# sanguino.net
KiCad netlist of a schematic drawn in EAGLE
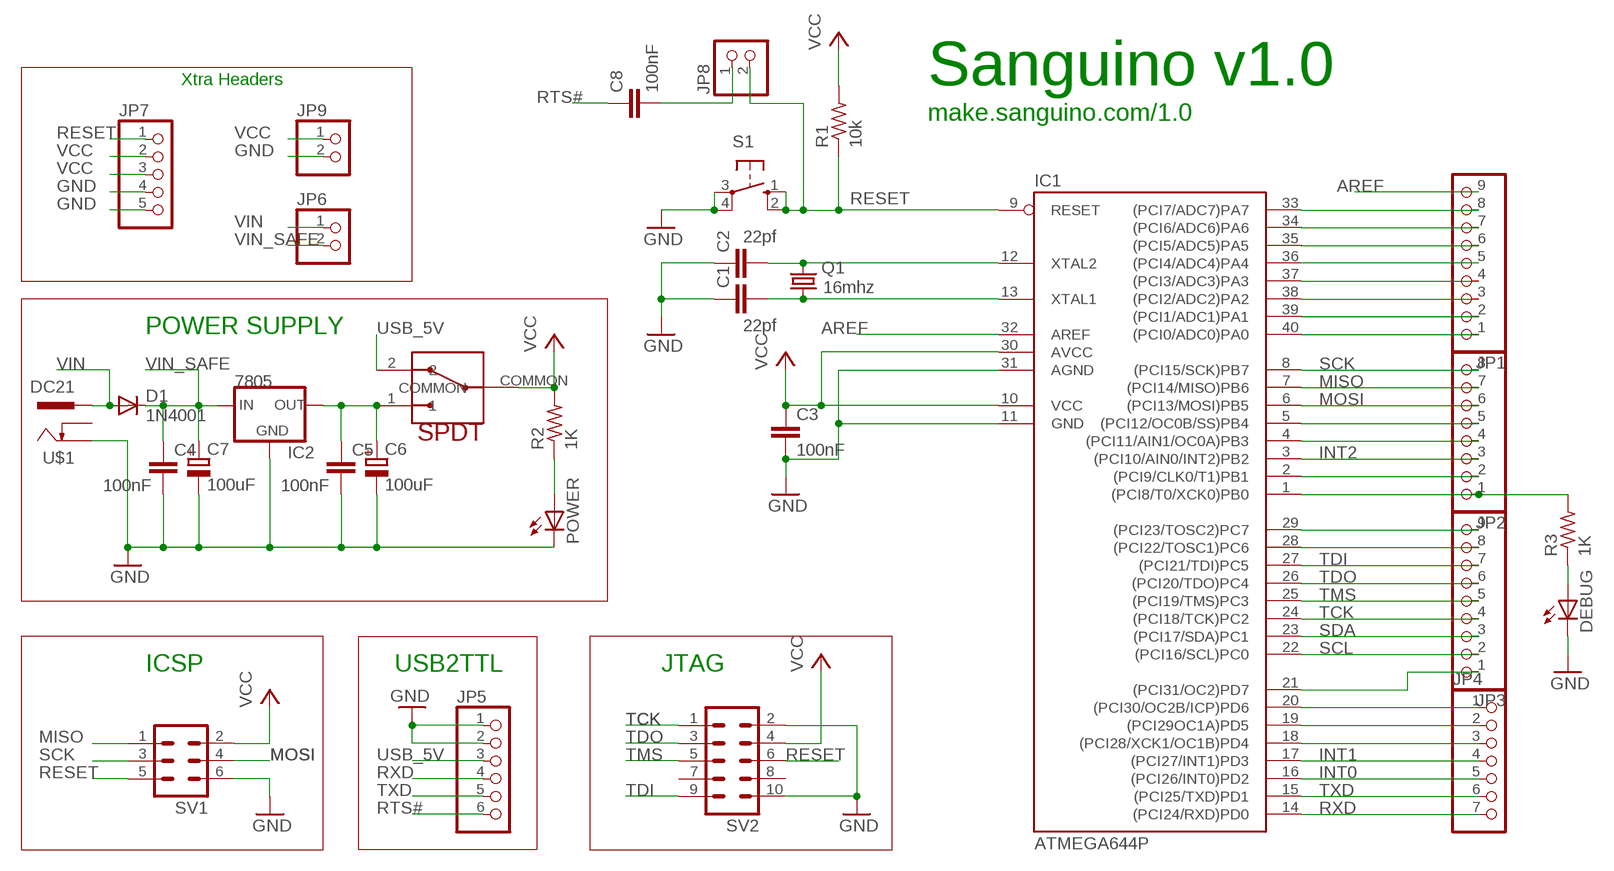
[diagram p0: schematic, sheet 1]

(export (version "E")
  (design (tool "Eeschema 10.0.6"))
  (components
    (comp (ref "C1")
      (value "22pf")
      (footprint "eagle-import:C025-025X050")
      (libsource (lib "eagle-import") (part "C-EU025-025X050"))
    )
    (comp (ref "C2")
      (value "22pf")
      (footprint "eagle-import:C025-025X050")
      (libsource (lib "eagle-import") (part "C-EU025-025X050"))
    )
    (comp (ref "C3")
      (value "100nF")
      (footprint "eagle-import:C050-030X075")
      (libsource (lib "eagle-import") (part "C-EU050-030X075"))
    )
    (comp (ref "C4")
      (value "100nF")
      (footprint "eagle-import:C050-030X075")
      (libsource (lib "eagle-import") (part "C-EU050-030X075"))
    )
    (comp (ref "C5")
      (value "100nF")
      (footprint "eagle-import:C050-030X075")
      (libsource (lib "eagle-import") (part "C-EU050-030X075"))
    )
    (comp (ref "C6")
      (value "100uF")
      (footprint "eagle-import:E2,5-6")
      (libsource (lib "eagle-import") (part "CPOL-EUE2.5-6"))
    )
    (comp (ref "C7")
      (value "100uF")
      (footprint "eagle-import:E2,5-6")
      (libsource (lib "eagle-import") (part "CPOL-EUE2.5-6"))
    )
    (comp (ref "C8")
      (value "100nF")
      (footprint "eagle-import:C050-030X075")
      (libsource (lib "eagle-import") (part "C-EU050-030X075"))
    )
    (comp (ref "D1")
      (value "1N4001")
      (footprint "eagle-import:DO41-10")
      (libsource (lib "eagle-import") (part "1N4004"))
    )
    (comp (ref "DEBUG")
      (value "LED3MM")
      (footprint "eagle-import:LED3MM")
      (libsource (lib "eagle-import") (part "LED3MM"))
    )
    (comp (ref "IC1")
      (value "ATMEGA644P")
      (footprint "eagle-import:DIL40")
      (libsource (lib "eagle-import") (part "ATMEGA644P-20"))
    )
    (comp (ref "IC2")
      (value "7805")
      (footprint "eagle-import:TO220-IGO")
      (libsource (lib "eagle-import") (part "V_REG_78XXSINK"))
    )
    (comp (ref "JP1")
      (value "PINHD-1X9")
      (footprint "eagle-import:1X09")
      (libsource (lib "eagle-import") (part "PINHD-1X9"))
    )
    (comp (ref "JP2")
      (value "PINHD-1X8")
      (footprint "eagle-import:1X08")
      (libsource (lib "eagle-import") (part "PINHD-1X8"))
    )
    (comp (ref "JP3")
      (value "PINHD-1X9")
      (footprint "eagle-import:1X09")
      (libsource (lib "eagle-import") (part "PINHD-1X9"))
    )
    (comp (ref "JP4")
      (value "PINHD-1X7")
      (footprint "eagle-import:1X07")
      (libsource (lib "eagle-import") (part "PINHD-1X7"))
    )
    (comp (ref "JP5")
      (value "PINHD-1X6")
      (footprint "eagle-import:1X06")
      (libsource (lib "eagle-import") (part "PINHD-1X6"))
    )
    (comp (ref "JP6")
      (value "PINHD-1X2")
      (footprint "eagle-import:1X02")
      (libsource (lib "eagle-import") (part "PINHD-1X2"))
    )
    (comp (ref "JP7")
      (value "PINHD-1X5")
      (footprint "eagle-import:1X05")
      (libsource (lib "eagle-import") (part "PINHD-1X5"))
    )
    (comp (ref "JP8")
      (value "PINHD-1X2")
      (footprint "eagle-import:1X02")
      (libsource (lib "eagle-import") (part "PINHD-1X2"))
    )
    (comp (ref "JP9")
      (value "PINHD-1X2")
      (footprint "eagle-import:1X02")
      (libsource (lib "eagle-import") (part "PINHD-1X2"))
    )
    (comp (ref "POWER")
      (value "LED3MM")
      (footprint "eagle-import:LED3MM")
      (libsource (lib "eagle-import") (part "LED3MM"))
    )
    (comp (ref "Q1")
      (value "16mhz")
      (footprint "eagle-import:HC49_S")
      (libsource (lib "eagle-import") (part "CRYSTALHC49S"))
    )
    (comp (ref "R1")
      (value "10k")
      (footprint "eagle-import:0207_7")
      (libsource (lib "eagle-import") (part "R-US_0207/7"))
    )
    (comp (ref "R2")
      (value "1K")
      (footprint "eagle-import:0207_2V")
      (libsource (lib "eagle-import") (part "R-US_0207/2V"))
    )
    (comp (ref "R3")
      (value "1K")
      (footprint "eagle-import:0207_2V")
      (libsource (lib "eagle-import") (part "resistor_R-US_0207/2V"))
    )
    (comp (ref "S1")
      (value "10-XX")
      (footprint "eagle-import:B3F-10XX")
      (libsource (lib "eagle-import") (part "10-XX"))
    )
    (comp (ref "SV1")
      (value "ML6")
      (footprint "eagle-import:ML6")
      (libsource (lib "eagle-import") (part "ML6"))
    )
    (comp (ref "SV2")
      (value "ML10")
      (footprint "eagle-import:ML10")
      (libsource (lib "eagle-import") (part "ML10"))
    )
    (comp (ref "U$1")
      (value "DC21")
      (footprint "eagle-import:DCSKT")
      (libsource (lib "eagle-import") (part "DC21"))
    )
    (comp (ref "U$2")
      (value "SPDT")
      (footprint "eagle-import:10SP001")
      (libsource (lib "eagle-import") (part "SPDT"))
    )
  )
  (nets
    (net (code "1") (name "/AREF") (class "Default")
      (node (ref "IC1") (pin "32") (pinfunction "AREF_32") (pintype "power_in"))
      (node (ref "JP1") (pin "9") (pinfunction "9_9") (pintype "passive"))
    )
    (net (code "2") (name "/INT0") (class "Default")
      (node (ref "IC1") (pin "16") (pinfunction "(PCI26/INT0)PD2_16") (pintype "bidirectional"))
      (node (ref "JP4") (pin "5") (pinfunction "5_5") (pintype "passive"))
    )
    (net (code "3") (name "/INT1") (class "Default")
      (node (ref "IC1") (pin "17") (pinfunction "(PCI27/INT1)PD3_17") (pintype "bidirectional"))
      (node (ref "JP4") (pin "4") (pinfunction "4_4") (pintype "passive"))
    )
    (net (code "4") (name "/INT2") (class "Default")
      (node (ref "IC1") (pin "3") (pinfunction "(PCI10/AIN0/INT2)PB2_3") (pintype "bidirectional"))
      (node (ref "JP2") (pin "3") (pinfunction "3_3") (pintype "passive"))
    )
    (net (code "5") (name "/MISO") (class "Default")
      (node (ref "IC1") (pin "7") (pinfunction "(PCI14/MISO)PB6_7") (pintype "bidirectional"))
      (node (ref "JP2") (pin "7") (pinfunction "7_7") (pintype "passive"))
      (node (ref "SV1") (pin "1") (pinfunction "1_1") (pintype "passive"))
    )
    (net (code "6") (name "/MOSI") (class "Default")
      (node (ref "IC1") (pin "6") (pinfunction "(PCI13/MOSI)PB5_6") (pintype "bidirectional"))
      (node (ref "JP2") (pin "6") (pinfunction "6_6") (pintype "passive"))
      (node (ref "SV1") (pin "4") (pinfunction "4_4") (pintype "passive"))
    )
    (net (code "7") (name "/RESET") (class "Default")
      (node (ref "IC1") (pin "9") (pinfunction "RESET_9") (pintype "input"))
      (node (ref "JP7") (pin "1") (pinfunction "1_1") (pintype "passive"))
      (node (ref "JP8") (pin "2") (pinfunction "2_2") (pintype "passive"))
      (node (ref "R1") (pin "1") (pinfunction "1_1") (pintype "passive"))
      (node (ref "S1") (pin "1") (pinfunction "S_1") (pintype "passive"))
      (node (ref "S1") (pin "2") (pinfunction "S1_2") (pintype "passive"))
      (node (ref "SV1") (pin "5") (pinfunction "5_5") (pintype "passive"))
      (node (ref "SV2") (pin "6") (pinfunction "6_6") (pintype "passive"))
    )
    (net (code "8") (name "/RTS#") (class "Default")
      (node (ref "C8") (pin "1") (pinfunction "1_1") (pintype "passive"))
      (node (ref "JP5") (pin "6") (pinfunction "6_6") (pintype "passive"))
    )
    (net (code "9") (name "/RXD") (class "Default")
      (node (ref "IC1") (pin "14") (pinfunction "(PCI24/RXD)PD0_14") (pintype "bidirectional"))
      (node (ref "JP4") (pin "7") (pinfunction "7_7") (pintype "passive"))
      (node (ref "JP5") (pin "4") (pinfunction "4_4") (pintype "passive"))
    )
    (net (code "10") (name "/SCK") (class "Default")
      (node (ref "IC1") (pin "8") (pinfunction "(PCI15/SCK)PB7_8") (pintype "bidirectional"))
      (node (ref "JP2") (pin "8") (pinfunction "8_8") (pintype "passive"))
      (node (ref "SV1") (pin "3") (pinfunction "3_3") (pintype "passive"))
    )
    (net (code "11") (name "/SCL") (class "Default")
      (node (ref "IC1") (pin "22") (pinfunction "(PCI16/SCL)PC0_22") (pintype "bidirectional"))
      (node (ref "JP3") (pin "2") (pinfunction "2_2") (pintype "passive"))
    )
    (net (code "12") (name "/SDA") (class "Default")
      (node (ref "IC1") (pin "23") (pinfunction "(PCI17/SDA)PC1_23") (pintype "bidirectional"))
      (node (ref "JP3") (pin "3") (pinfunction "3_3") (pintype "passive"))
    )
    (net (code "13") (name "/TCK") (class "Default")
      (node (ref "IC1") (pin "24") (pinfunction "(PCI18/TCK)PC2_24") (pintype "bidirectional"))
      (node (ref "JP3") (pin "4") (pinfunction "4_4") (pintype "passive"))
      (node (ref "SV2") (pin "1") (pinfunction "1_1") (pintype "passive"))
    )
    (net (code "14") (name "/TDI") (class "Default")
      (node (ref "IC1") (pin "27") (pinfunction "(PCI21/TDI)PC5_27") (pintype "bidirectional"))
      (node (ref "JP3") (pin "7") (pinfunction "7_7") (pintype "passive"))
      (node (ref "SV2") (pin "9") (pinfunction "9_9") (pintype "passive"))
    )
    (net (code "15") (name "/TDO") (class "Default")
      (node (ref "IC1") (pin "26") (pinfunction "(PCI20/TDO)PC4_26") (pintype "bidirectional"))
      (node (ref "JP3") (pin "6") (pinfunction "6_6") (pintype "passive"))
      (node (ref "SV2") (pin "3") (pinfunction "3_3") (pintype "passive"))
    )
    (net (code "16") (name "/TMS") (class "Default")
      (node (ref "IC1") (pin "25") (pinfunction "(PCI19/TMS)PC3_25") (pintype "bidirectional"))
      (node (ref "JP3") (pin "5") (pinfunction "5_5") (pintype "passive"))
      (node (ref "SV2") (pin "5") (pinfunction "5_5") (pintype "passive"))
    )
    (net (code "17") (name "/TXD") (class "Default")
      (node (ref "IC1") (pin "15") (pinfunction "(PCI25/TXD)PD1_15") (pintype "bidirectional"))
      (node (ref "JP4") (pin "6") (pinfunction "6_6") (pintype "passive"))
      (node (ref "JP5") (pin "5") (pinfunction "5_5") (pintype "passive"))
    )
    (net (code "18") (name "/USB_5V") (class "Default")
      (node (ref "JP5") (pin "3") (pinfunction "3_3") (pintype "passive"))
      (node (ref "U$2") (pin "2") (pinfunction "2_2") (pintype "bidirectional"))
    )
    (net (code "19") (name "/VIN") (class "Default")
      (node (ref "D1") (pin "A") (pinfunction "A_A") (pintype "passive"))
      (node (ref "JP6") (pin "1") (pinfunction "1_1") (pintype "passive"))
      (node (ref "U$1") (pin "1") (pinfunction "1_1") (pintype "passive"))
    )
    (net (code "20") (name "/VIN_SAFE") (class "Default")
      (node (ref "C4") (pin "1") (pinfunction "1_1") (pintype "passive"))
      (node (ref "C7") (pin "+") (pinfunction "+_+") (pintype "passive"))
      (node (ref "D1") (pin "C") (pinfunction "C_C") (pintype "passive"))
      (node (ref "IC2") (pin "IN") (pinfunction "IN_IN") (pintype "input"))
      (node (ref "JP6") (pin "2") (pinfunction "2_2") (pintype "passive"))
    )
    (net (code "21") (name "GND") (class "Default")
      (node (ref "C1") (pin "1") (pinfunction "1_1") (pintype "passive"))
      (node (ref "C2") (pin "1") (pinfunction "1_1") (pintype "passive"))
      (node (ref "C3") (pin "2") (pinfunction "2_2") (pintype "passive"))
      (node (ref "C4") (pin "2") (pinfunction "2_2") (pintype "passive"))
      (node (ref "C5") (pin "2") (pinfunction "2_2") (pintype "passive"))
      (node (ref "C6") (pin "-") (pinfunction "-_-") (pintype "passive"))
      (node (ref "C7") (pin "-") (pinfunction "-_-") (pintype "passive"))
      (node (ref "DEBUG") (pin "K") (pinfunction "C_K") (pintype "passive"))
      (node (ref "IC1") (pin "11") (pinfunction "GND_11") (pintype "power_in"))
      (node (ref "IC1") (pin "31") (pinfunction "AGND_31") (pintype "power_in"))
      (node (ref "IC2") (pin "GND") (pinfunction "GND_GND") (pintype "input"))
      (node (ref "JP5") (pin "1") (pinfunction "1_1") (pintype "passive"))
      (node (ref "JP5") (pin "2") (pinfunction "2_2") (pintype "passive"))
      (node (ref "JP7") (pin "4") (pinfunction "4_4") (pintype "passive"))
      (node (ref "JP7") (pin "5") (pinfunction "5_5") (pintype "passive"))
      (node (ref "JP9") (pin "2") (pinfunction "2_2") (pintype "passive"))
      (node (ref "POWER") (pin "K") (pinfunction "C_K") (pintype "passive"))
      (node (ref "S1") (pin "3") (pinfunction "P_3") (pintype "passive"))
      (node (ref "S1") (pin "4") (pinfunction "P1_4") (pintype "passive"))
      (node (ref "SV1") (pin "6") (pinfunction "6_6") (pintype "passive"))
      (node (ref "SV2") (pin "10") (pinfunction "10_10") (pintype "passive"))
      (node (ref "SV2") (pin "2") (pinfunction "2_2") (pintype "passive"))
      (node (ref "U$1") (pin "2") (pinfunction "2_2") (pintype "passive"))
    )
    (net (code "22") (name "Net-(C5-Pad1)") (class "Default")
      (node (ref "C5") (pin "1") (pinfunction "1_1") (pintype "passive"))
      (node (ref "C6") (pin "+") (pinfunction "+_+") (pintype "passive"))
      (node (ref "IC2") (pin "OUT") (pinfunction "OUT_OUT") (pintype "output"))
      (node (ref "U$2") (pin "1") (pinfunction "1_1") (pintype "bidirectional"))
    )
    (net (code "23") (name "Net-(C8-Pad2)") (class "Default")
      (node (ref "C8") (pin "2") (pinfunction "2_2") (pintype "passive"))
      (node (ref "JP8") (pin "1") (pinfunction "1_1") (pintype "passive"))
    )
    (net (code "24") (name "Net-(DEBUG-PadA)") (class "Default")
      (node (ref "DEBUG") (pin "A") (pinfunction "A_A") (pintype "passive"))
      (node (ref "R3") (pin "1") (pinfunction "1_1") (pintype "passive"))
    )
    (net (code "25") (name "Net-(IC1-(PCI0{slash}ADC0)PA0)") (class "Default")
      (node (ref "IC1") (pin "40") (pinfunction "(PCI0/ADC0)PA0_40") (pintype "bidirectional"))
      (node (ref "JP1") (pin "1") (pinfunction "1_1") (pintype "passive"))
    )
    (net (code "26") (name "Net-(IC1-(PCI1{slash}ADC1)PA1)") (class "Default")
      (node (ref "IC1") (pin "39") (pinfunction "(PCI1/ADC1)PA1_39") (pintype "bidirectional"))
      (node (ref "JP1") (pin "2") (pinfunction "2_2") (pintype "passive"))
    )
    (net (code "27") (name "Net-(IC1-(PCI2{slash}ADC2)PA2)") (class "Default")
      (node (ref "IC1") (pin "38") (pinfunction "(PCI2/ADC2)PA2_38") (pintype "bidirectional"))
      (node (ref "JP1") (pin "3") (pinfunction "3_3") (pintype "passive"))
    )
    (net (code "28") (name "Net-(IC1-(PCI3{slash}ADC3)PA3)") (class "Default")
      (node (ref "IC1") (pin "37") (pinfunction "(PCI3/ADC3)PA3_37") (pintype "bidirectional"))
      (node (ref "JP1") (pin "4") (pinfunction "4_4") (pintype "passive"))
    )
    (net (code "29") (name "Net-(IC1-(PCI4{slash}ADC4)PA4)") (class "Default")
      (node (ref "IC1") (pin "36") (pinfunction "(PCI4/ADC4)PA4_36") (pintype "bidirectional"))
      (node (ref "JP1") (pin "5") (pinfunction "5_5") (pintype "passive"))
    )
    (net (code "30") (name "Net-(IC1-(PCI5{slash}ADC5)PA5)") (class "Default")
      (node (ref "IC1") (pin "35") (pinfunction "(PCI5/ADC5)PA5_35") (pintype "bidirectional"))
      (node (ref "JP1") (pin "6") (pinfunction "6_6") (pintype "passive"))
    )
    (net (code "31") (name "Net-(IC1-(PCI6{slash}ADC6)PA6)") (class "Default")
      (node (ref "IC1") (pin "34") (pinfunction "(PCI6/ADC6)PA6_34") (pintype "bidirectional"))
      (node (ref "JP1") (pin "7") (pinfunction "7_7") (pintype "passive"))
    )
    (net (code "32") (name "Net-(IC1-(PCI7{slash}ADC7)PA7)") (class "Default")
      (node (ref "IC1") (pin "33") (pinfunction "(PCI7/ADC7)PA7_33") (pintype "bidirectional"))
      (node (ref "JP1") (pin "8") (pinfunction "8_8") (pintype "passive"))
    )
    (net (code "33") (name "Net-(IC1-(PCI8{slash}T0{slash}XCK0)PB0)") (class "Default")
      (node (ref "IC1") (pin "1") (pinfunction "(PCI8/T0/XCK0)PB0_1") (pintype "bidirectional"))
      (node (ref "JP2") (pin "1") (pinfunction "1_1") (pintype "passive"))
      (node (ref "R3") (pin "2") (pinfunction "2_2") (pintype "passive"))
    )
    (net (code "34") (name "Net-(IC1-(PCI9{slash}CLK0{slash}T1)PB1)") (class "Default")
      (node (ref "IC1") (pin "2") (pinfunction "(PCI9/CLK0/T1)PB1_2") (pintype "bidirectional"))
      (node (ref "JP2") (pin "2") (pinfunction "2_2") (pintype "passive"))
    )
    (net (code "35") (name "Net-(IC1-(PCI11{slash}AIN1{slash}OC0A)PB3)") (class "Default")
      (node (ref "IC1") (pin "4") (pinfunction "(PCI11/AIN1/OC0A)PB3_4") (pintype "bidirectional"))
      (node (ref "JP2") (pin "4") (pinfunction "4_4") (pintype "passive"))
    )
    (net (code "36") (name "Net-(IC1-(PCI12{slash}OC0B{slash}SS)PB4)") (class "Default")
      (node (ref "IC1") (pin "5") (pinfunction "(PCI12/OC0B/SS)PB4_5") (pintype "bidirectional"))
      (node (ref "JP2") (pin "5") (pinfunction "5_5") (pintype "passive"))
    )
    (net (code "37") (name "Net-(IC1-(PCI22{slash}TOSC1)PC6)") (class "Default")
      (node (ref "IC1") (pin "28") (pinfunction "(PCI22/TOSC1)PC6_28") (pintype "bidirectional"))
      (node (ref "JP3") (pin "8") (pinfunction "8_8") (pintype "passive"))
    )
    (net (code "38") (name "Net-(IC1-(PCI23{slash}TOSC2)PC7)") (class "Default")
      (node (ref "IC1") (pin "29") (pinfunction "(PCI23/TOSC2)PC7_29") (pintype "bidirectional"))
      (node (ref "JP3") (pin "9") (pinfunction "9_9") (pintype "passive"))
    )
    (net (code "39") (name "Net-(IC1-(PCI28{slash}XCK1{slash}OC1B)PD4)") (class "Default")
      (node (ref "IC1") (pin "18") (pinfunction "(PCI28/XCK1/OC1B)PD4_18") (pintype "bidirectional"))
      (node (ref "JP4") (pin "3") (pinfunction "3_3") (pintype "passive"))
    )
    (net (code "40") (name "Net-(IC1-(PCI29OC1A)PD5)") (class "Default")
      (node (ref "IC1") (pin "19") (pinfunction "(PCI29OC1A)PD5_19") (pintype "bidirectional"))
      (node (ref "JP4") (pin "2") (pinfunction "2_2") (pintype "passive"))
    )
    (net (code "41") (name "Net-(IC1-(PCI30{slash}OC2B{slash}ICP)PD6)") (class "Default")
      (node (ref "IC1") (pin "20") (pinfunction "(PCI30/OC2B/ICP)PD6_20") (pintype "bidirectional"))
      (node (ref "JP4") (pin "1") (pinfunction "1_1") (pintype "passive"))
    )
    (net (code "42") (name "Net-(IC1-(PCI31{slash}OC2)PD7)") (class "Default")
      (node (ref "IC1") (pin "21") (pinfunction "(PCI31/OC2)PD7_21") (pintype "bidirectional"))
      (node (ref "JP3") (pin "1") (pinfunction "1_1") (pintype "passive"))
    )
    (net (code "43") (name "Net-(IC1-XTAL1)") (class "Default")
      (node (ref "C1") (pin "2") (pinfunction "2_2") (pintype "passive"))
      (node (ref "IC1") (pin "13") (pinfunction "XTAL1_13") (pintype "bidirectional"))
      (node (ref "Q1") (pin "1") (pinfunction "1_1") (pintype "passive"))
    )
    (net (code "44") (name "Net-(IC1-XTAL2)") (class "Default")
      (node (ref "C2") (pin "2") (pinfunction "2_2") (pintype "passive"))
      (node (ref "IC1") (pin "12") (pinfunction "XTAL2_12") (pintype "bidirectional"))
      (node (ref "Q1") (pin "2") (pinfunction "2_2") (pintype "passive"))
    )
    (net (code "45") (name "Net-(POWER-PadA)") (class "Default")
      (node (ref "POWER") (pin "A") (pinfunction "A_A") (pintype "passive"))
      (node (ref "R2") (pin "1") (pinfunction "1_1") (pintype "passive"))
    )
    (net (code "46") (name "VCC") (class "Default")
      (node (ref "C3") (pin "1") (pinfunction "1_1") (pintype "passive"))
      (node (ref "IC1") (pin "10") (pinfunction "VCC_10") (pintype "power_in"))
      (node (ref "IC1") (pin "30") (pinfunction "AVCC_30") (pintype "power_in"))
      (node (ref "JP7") (pin "2") (pinfunction "2_2") (pintype "passive"))
      (node (ref "JP7") (pin "3") (pinfunction "3_3") (pintype "passive"))
      (node (ref "JP9") (pin "1") (pinfunction "1_1") (pintype "passive"))
      (node (ref "R1") (pin "2") (pinfunction "2_2") (pintype "passive"))
      (node (ref "R2") (pin "2") (pinfunction "2_2") (pintype "passive"))
      (node (ref "SV1") (pin "2") (pinfunction "2_2") (pintype "passive"))
      (node (ref "SV2") (pin "4") (pinfunction "4_4") (pintype "passive"))
      (node (ref "U$2") (pin "COMMON") (pinfunction "COMMON_COMMON") (pintype "bidirectional"))
    )
    (net (code "47") (name "unconnected-(SV2-Pad7)") (class "Default")
      (node (ref "SV2") (pin "7") (pinfunction "7_7") (pintype "passive"))
    )
    (net (code "48") (name "unconnected-(SV2-Pad8)") (class "Default")
      (node (ref "SV2") (pin "8") (pinfunction "8_8") (pintype "passive"))
    )
    (net (code "49") (name "unconnected-(U$1-Pad3)") (class "Default")
      (node (ref "U$1") (pin "3") (pinfunction "3_3") (pintype "passive"))
    )
  )
)
